# vga2.net
KiCad netlist of a schematic drawn in EAGLE
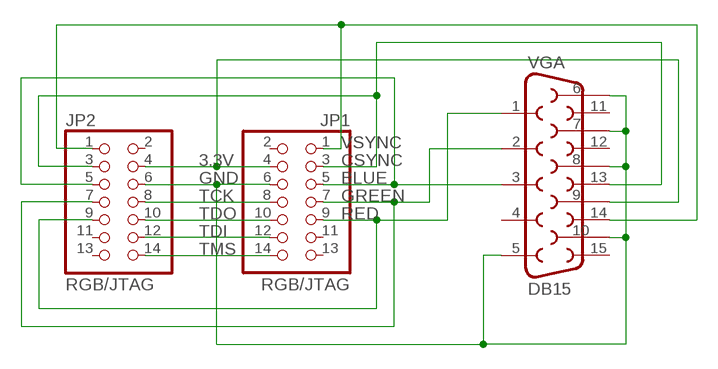
[diagram p0: schematic, sheet 1]

(export (version "E")
  (design (tool "Eeschema 10.0.6"))
  (components
    (comp (ref "JP1")
      (value "RGB/JTAG")
      (footprint "eagle-import:2X07")
      (libsource (lib "eagle-import") (part "PINHD-2X7"))
    )
    (comp (ref "JP2")
      (value "RGB/JTAG")
      (footprint "eagle-import:2X07")
      (libsource (lib "eagle-import") (part "PINHD-2X7"))
    )
    (comp (ref "VGA")
      (value "DB15")
      (footprint "eagle-import:DB15")
      (libsource (lib "eagle-import") (part "DB15"))
    )
  )
  (nets
    (net (code "1") (name "/3.3V") (class "Default")
      (node (ref "JP1") (pin "4") (pinfunction "4_4") (pintype "passive"))
      (node (ref "JP2") (pin "4") (pinfunction "4_4") (pintype "passive"))
      (node (ref "VGA") (pin "9") (pinfunction "9_9") (pintype "passive"))
    )
    (net (code "2") (name "/BLUE") (class "Default")
      (node (ref "JP1") (pin "5") (pinfunction "5_5") (pintype "passive"))
      (node (ref "JP2") (pin "5") (pinfunction "5_5") (pintype "passive"))
      (node (ref "VGA") (pin "3") (pinfunction "3_3") (pintype "passive"))
    )
    (net (code "3") (name "/CSYNC") (class "Default")
      (node (ref "JP1") (pin "3") (pinfunction "3_3") (pintype "passive"))
      (node (ref "JP2") (pin "3") (pinfunction "3_3") (pintype "passive"))
      (node (ref "VGA") (pin "13") (pinfunction "13_13") (pintype "passive"))
    )
    (net (code "4") (name "/GND") (class "Default")
      (node (ref "JP1") (pin "6") (pinfunction "6_6") (pintype "passive"))
      (node (ref "JP2") (pin "6") (pinfunction "6_6") (pintype "passive"))
      (node (ref "VGA") (pin "10") (pinfunction "10_10") (pintype "passive"))
      (node (ref "VGA") (pin "5") (pinfunction "5_5") (pintype "passive"))
      (node (ref "VGA") (pin "6") (pinfunction "6_6") (pintype "passive"))
      (node (ref "VGA") (pin "7") (pinfunction "7_7") (pintype "passive"))
      (node (ref "VGA") (pin "8") (pinfunction "8_8") (pintype "passive"))
    )
    (net (code "5") (name "/GREEN") (class "Default")
      (node (ref "JP1") (pin "7") (pinfunction "7_7") (pintype "passive"))
      (node (ref "JP2") (pin "7") (pinfunction "7_7") (pintype "passive"))
      (node (ref "VGA") (pin "2") (pinfunction "2_2") (pintype "passive"))
    )
    (net (code "6") (name "/RED") (class "Default")
      (node (ref "JP1") (pin "9") (pinfunction "9_9") (pintype "passive"))
      (node (ref "JP2") (pin "9") (pinfunction "9_9") (pintype "passive"))
      (node (ref "VGA") (pin "1") (pinfunction "1_1") (pintype "passive"))
    )
    (net (code "7") (name "/TCK") (class "Default")
      (node (ref "JP1") (pin "8") (pinfunction "8_8") (pintype "passive"))
      (node (ref "JP2") (pin "8") (pinfunction "8_8") (pintype "passive"))
    )
    (net (code "8") (name "/TDI") (class "Default")
      (node (ref "JP1") (pin "12") (pinfunction "12_12") (pintype "passive"))
      (node (ref "JP2") (pin "12") (pinfunction "12_12") (pintype "passive"))
    )
    (net (code "9") (name "/TDO") (class "Default")
      (node (ref "JP1") (pin "10") (pinfunction "10_10") (pintype "passive"))
      (node (ref "JP2") (pin "10") (pinfunction "10_10") (pintype "passive"))
    )
    (net (code "10") (name "/TMS") (class "Default")
      (node (ref "JP1") (pin "14") (pinfunction "14_14") (pintype "passive"))
      (node (ref "JP2") (pin "14") (pinfunction "14_14") (pintype "passive"))
    )
    (net (code "11") (name "/VSYNC") (class "Default")
      (node (ref "JP1") (pin "1") (pinfunction "1_1") (pintype "passive"))
      (node (ref "JP2") (pin "1") (pinfunction "1_1") (pintype "passive"))
      (node (ref "VGA") (pin "14") (pinfunction "14_14") (pintype "passive"))
    )
    (net (code "12") (name "unconnected-(JP1-Pad2)") (class "Default")
      (node (ref "JP1") (pin "2") (pinfunction "2_2") (pintype "passive"))
    )
    (net (code "13") (name "unconnected-(JP1-Pad11)") (class "Default")
      (node (ref "JP1") (pin "11") (pinfunction "11_11") (pintype "passive"))
    )
    (net (code "14") (name "unconnected-(JP1-Pad13)") (class "Default")
      (node (ref "JP1") (pin "13") (pinfunction "13_13") (pintype "passive"))
    )
    (net (code "15") (name "unconnected-(JP2-Pad2)") (class "Default")
      (node (ref "JP2") (pin "2") (pinfunction "2_2") (pintype "passive"))
    )
    (net (code "16") (name "unconnected-(JP2-Pad11)") (class "Default")
      (node (ref "JP2") (pin "11") (pinfunction "11_11") (pintype "passive"))
    )
    (net (code "17") (name "unconnected-(JP2-Pad13)") (class "Default")
      (node (ref "JP2") (pin "13") (pinfunction "13_13") (pintype "passive"))
    )
    (net (code "18") (name "unconnected-(VGA-Pad4)") (class "Default")
      (node (ref "VGA") (pin "4") (pinfunction "4_4") (pintype "passive"))
    )
    (net (code "19") (name "unconnected-(VGA-Pad11)") (class "Default")
      (node (ref "VGA") (pin "11") (pinfunction "11_11") (pintype "passive"))
    )
    (net (code "20") (name "unconnected-(VGA-Pad12)") (class "Default")
      (node (ref "VGA") (pin "12") (pinfunction "12_12") (pintype "passive"))
    )
    (net (code "21") (name "unconnected-(VGA-Pad15)") (class "Default")
      (node (ref "VGA") (pin "15") (pinfunction "15_15") (pintype "passive"))
    )
  )
)
